# 15_LCD.net
KiCad netlist of a schematic drawn in Altium Designer
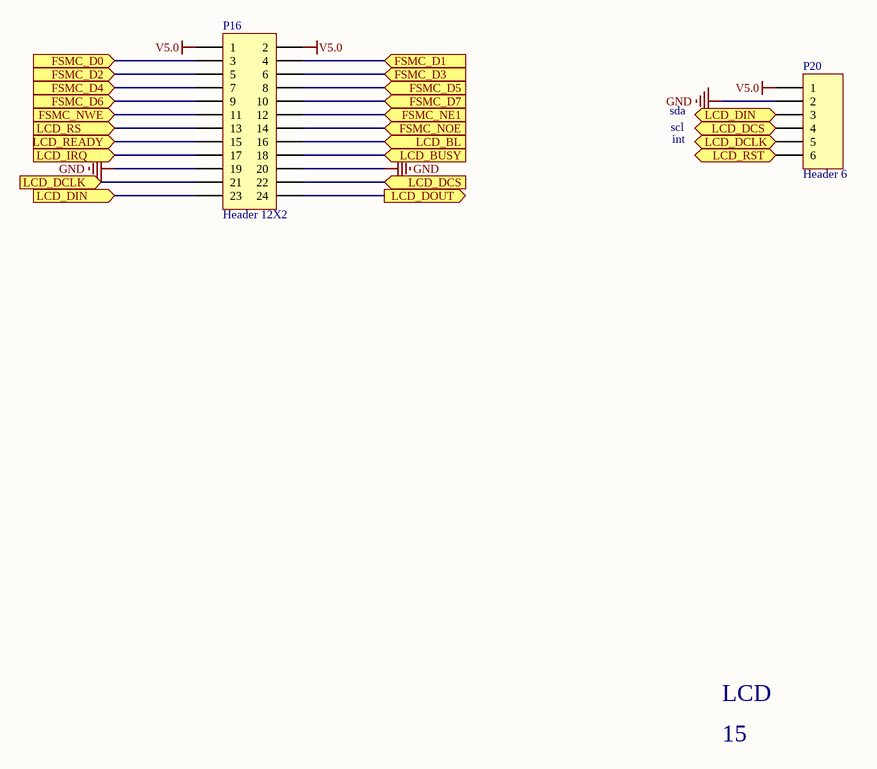
[diagram p0: 15_LCD.SchDoc]

(export (version "E")
  (design (tool "Eeschema 10.0.6"))
  (components
    (comp (ref "P16")
      (value "Header 12X2")
      (footprint "HDR2X12")
      (description "Header, 12-Pin, Dual row")
      (fields (field (name "PUBLISHER") "Altium Limited"))
      (libsource (lib "Miscellaneous Connectors") (part "Header 12X2"))
    )
    (comp (ref "P20")
      (value "Header 6")
      (footprint "6X2MMZ")
      (description "Header, 6-Pin")
      (fields (field (name "PUBLISHER") "Altium Limited"))
      (libsource (lib "Miscellaneous Connectors") (part "Header 6"))
    )
  )
  (nets
    (net (code "1") (name "/FSMC_D0") (class "Default")
      (node (ref "P16") (pin "3") (pinfunction "3_3") (pintype "passive"))
    )
    (net (code "2") (name "/FSMC_D1") (class "Default")
      (node (ref "P16") (pin "4") (pinfunction "4_4") (pintype "passive"))
    )
    (net (code "3") (name "/FSMC_D2") (class "Default")
      (node (ref "P16") (pin "5") (pinfunction "5_5") (pintype "passive"))
    )
    (net (code "4") (name "/FSMC_D3") (class "Default")
      (node (ref "P16") (pin "6") (pinfunction "6_6") (pintype "passive"))
    )
    (net (code "5") (name "/FSMC_D4") (class "Default")
      (node (ref "P16") (pin "7") (pinfunction "7_7") (pintype "passive"))
    )
    (net (code "6") (name "/FSMC_D5") (class "Default")
      (node (ref "P16") (pin "8") (pinfunction "8_8") (pintype "passive"))
    )
    (net (code "7") (name "/FSMC_D6") (class "Default")
      (node (ref "P16") (pin "9") (pinfunction "9_9") (pintype "passive"))
    )
    (net (code "8") (name "/FSMC_D7") (class "Default")
      (node (ref "P16") (pin "10") (pinfunction "10_10") (pintype "passive"))
    )
    (net (code "9") (name "/FSMC_NE1") (class "Default")
      (node (ref "P16") (pin "12") (pinfunction "12_12") (pintype "passive"))
    )
    (net (code "10") (name "/FSMC_NOE") (class "Default")
      (node (ref "P16") (pin "14") (pinfunction "14_14") (pintype "passive"))
    )
    (net (code "11") (name "/FSMC_NWE") (class "Default")
      (node (ref "P16") (pin "11") (pinfunction "11_11") (pintype "passive"))
    )
    (net (code "12") (name "/LCD_BL") (class "Default")
      (node (ref "P16") (pin "16") (pinfunction "16_16") (pintype "passive"))
    )
    (net (code "13") (name "/LCD_BUSY") (class "Default")
      (node (ref "P16") (pin "18") (pinfunction "18_18") (pintype "passive"))
    )
    (net (code "14") (name "/LCD_DCLK") (class "Default")
      (node (ref "P16") (pin "21") (pinfunction "21_21") (pintype "passive"))
      (node (ref "P20") (pin "5") (pinfunction "5_5") (pintype "passive"))
    )
    (net (code "15") (name "/LCD_DCS") (class "Default")
      (node (ref "P16") (pin "22") (pinfunction "22_22") (pintype "passive"))
      (node (ref "P20") (pin "4") (pinfunction "4_4") (pintype "passive"))
    )
    (net (code "16") (name "/LCD_DIN") (class "Default")
      (node (ref "P16") (pin "23") (pinfunction "23_23") (pintype "passive"))
      (node (ref "P20") (pin "3") (pinfunction "3_3") (pintype "passive"))
    )
    (net (code "17") (name "/LCD_DOUT") (class "Default")
      (node (ref "P16") (pin "24") (pinfunction "24_24") (pintype "passive"))
    )
    (net (code "18") (name "/LCD_IRQ") (class "Default")
      (node (ref "P16") (pin "17") (pinfunction "17_17") (pintype "passive"))
    )
    (net (code "19") (name "/LCD_READY") (class "Default")
      (node (ref "P16") (pin "15") (pinfunction "15_15") (pintype "passive"))
    )
    (net (code "20") (name "/LCD_RS") (class "Default")
      (node (ref "P16") (pin "13") (pinfunction "13_13") (pintype "passive"))
    )
    (net (code "21") (name "/LCD_RST") (class "Default")
      (node (ref "P20") (pin "6") (pinfunction "6_6") (pintype "passive"))
    )
    (net (code "22") (name "GND") (class "Default")
      (node (ref "P16") (pin "19") (pinfunction "19_19") (pintype "passive"))
      (node (ref "P16") (pin "20") (pinfunction "20_20") (pintype "passive"))
      (node (ref "P20") (pin "2") (pinfunction "2_2") (pintype "passive"))
    )
    (net (code "23") (name "V5.0") (class "Default")
      (node (ref "P16") (pin "1") (pinfunction "1_1") (pintype "passive"))
      (node (ref "P16") (pin "2") (pinfunction "2_2") (pintype "passive"))
      (node (ref "P20") (pin "1") (pinfunction "1_1") (pintype "passive"))
    )
  )
)
